# flex_sensor_wheatstone.net
KiCad netlist of a schematic drawn in EAGLE
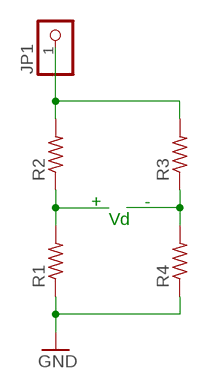
[diagram p0: schematic, sheet 1]

(export (version "E")
  (design (tool "Eeschema 10.0.6"))
  (components
    (comp (ref "JP1")
      (value "PINHD-1X1")
      (footprint "eagle-import:1X01")
      (libsource (lib "eagle-import") (part "PINHD-1X1"))
    )
    (comp (ref "R1")
      (value "R-US_0207/5V")
      (footprint "eagle-import:0207_5V")
      (libsource (lib "eagle-import") (part "R-US_0207/5V"))
    )
    (comp (ref "R2")
      (value "R-US_0207/5V")
      (footprint "eagle-import:0207_5V")
      (libsource (lib "eagle-import") (part "R-US_0207/5V"))
    )
    (comp (ref "R3")
      (value "R-US_0207/7")
      (footprint "eagle-import:0207_7")
      (libsource (lib "eagle-import") (part "R-US_0207/7"))
    )
    (comp (ref "R4")
      (value "R-US_0207/7")
      (footprint "eagle-import:0207_7")
      (libsource (lib "eagle-import") (part "R-US_0207/7"))
    )
  )
  (nets
    (net (code "1") (name "GND") (class "Default")
      (node (ref "R1") (pin "1") (pinfunction "1_1") (pintype "passive"))
      (node (ref "R4") (pin "1") (pinfunction "1_1") (pintype "passive"))
    )
    (net (code "2") (name "Net-(JP1-Pad1)") (class "Default")
      (node (ref "JP1") (pin "1") (pinfunction "1_1") (pintype "passive"))
      (node (ref "R2") (pin "2") (pinfunction "2_2") (pintype "passive"))
      (node (ref "R3") (pin "2") (pinfunction "2_2") (pintype "passive"))
    )
    (net (code "3") (name "Net-(R1-Pad2)") (class "Default")
      (node (ref "R1") (pin "2") (pinfunction "2_2") (pintype "passive"))
      (node (ref "R2") (pin "1") (pinfunction "1_1") (pintype "passive"))
    )
    (net (code "4") (name "Net-(R3-Pad1)") (class "Default")
      (node (ref "R3") (pin "1") (pinfunction "1_1") (pintype "passive"))
      (node (ref "R4") (pin "2") (pinfunction "2_2") (pintype "passive"))
    )
  )
)
